# osd.net
KiCad netlist of a schematic drawn in Altium Designer
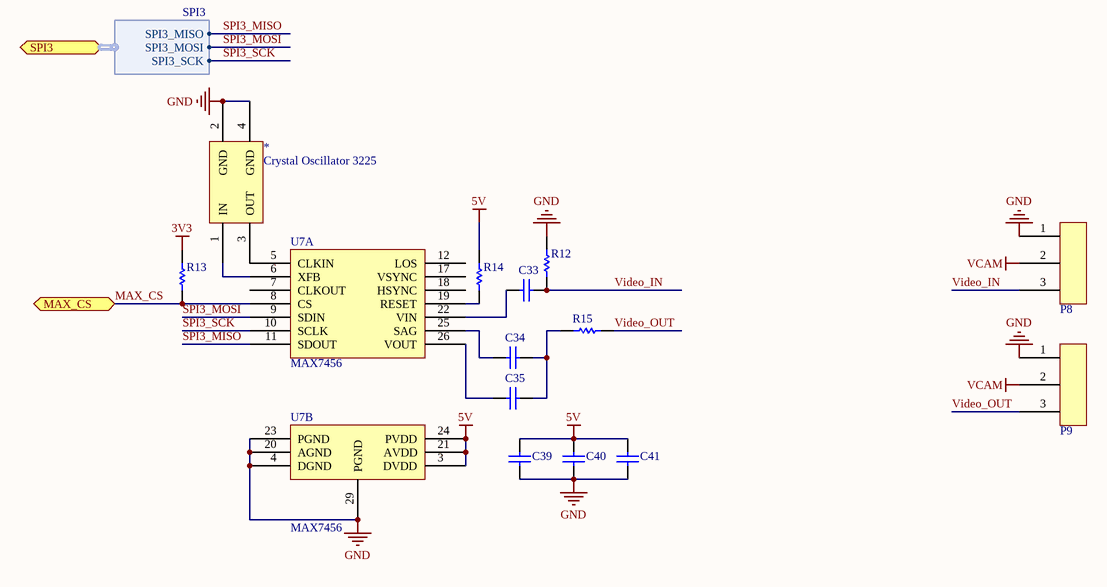
[diagram p0: osd.SchDoc]

(export (version "E")
  (design (tool "Eeschema 10.0.6"))
  (components
    (comp (ref "*")
      (value "Crystal Oscillator 3225")
      (footprint "TSX-3225")
      (description "TSX-3225")
      (libsource (lib "other") (part "TSX-3225"))
    )
    (comp (ref "C33")
      (value "CAP 100nF 25V 0603(1608)")
      (footprint "CAPC0603(1608)100_N")
      (description "CAP 100nF 25V ±20% 0603 (1608 Metric) Thickness 1mm SMD")
      (fields (field (name "TOLERANCE") "Â±20%"))
      (libsource (lib "Altium Content Vault") (part "CAP"))
    )
    (comp (ref "C34")
      (value "CAP 47uF 16V 1206(3216)")
      (footprint "CAPC1206(3216)190_M")
      (description "CAP 47uF 16V ±20% 1206 (3216 Metric) Thickness 1.9mm SMD")
      (fields (field (name "TOLERANCE") "Â±20%"))
      (libsource (lib "Altium Content Vault") (part "CAP"))
    )
    (comp (ref "C35")
      (value "CAP 47uF 16V 1206(3216)")
      (footprint "CAPC1206(3216)190_M")
      (description "CAP 47uF 16V ±20% 1206 (3216 Metric) Thickness 1.9mm SMD")
      (fields (field (name "TOLERANCE") "Â±20%"))
      (libsource (lib "Altium Content Vault") (part "CAP"))
    )
    (comp (ref "C39")
      (value "CAP 100nF 35V 0402(1005)")
      (footprint "CAPC0402(1005)60_N")
      (description "CAP 100nF 35V ±10% 0402 (1005 Metric) Thickness 0.6mm SMD")
      (fields (field (name "TOLERANCE") "Â±10%"))
      (libsource (lib "Altium Content Vault") (part "CAP"))
    )
    (comp (ref "C40")
      (value "CAP 100nF 35V 0402(1005)")
      (footprint "CAPC0402(1005)60_N")
      (description "CAP 100nF 35V ±10% 0402 (1005 Metric) Thickness 0.6mm SMD")
      (fields (field (name "TOLERANCE") "Â±10%"))
      (libsource (lib "Altium Content Vault") (part "CAP"))
    )
    (comp (ref "C41")
      (value "CAP 100nF 35V 0402(1005)")
      (footprint "CAPC0402(1005)60_N")
      (description "CAP 100nF 35V ±10% 0402 (1005 Metric) Thickness 0.6mm SMD")
      (fields (field (name "TOLERANCE") "Â±10%"))
      (libsource (lib "Altium Content Vault") (part "CAP"))
    )
    (comp (ref "P8") (value "3 Pads") (footprint "3Pads") (libsource (lib "MyLib") (part "3 Pads")))
    (comp (ref "P9") (value "3 Pads") (footprint "3Pads") (libsource (lib "MyLib") (part "3 Pads")))
    (comp (ref "R12")
      (value "75R 5% 0603(1608)")
      (footprint "RESC0603(1608)_N")
      (description "75R 0.1W 5% 0603 (1608 Metric)  SMD")
      (fields (field (name "TOLERANCE") "5 %") (field (name "POWER") "0.1 W"))
      (libsource (lib "Altium Content Vault") (part "RES"))
    )
    (comp (ref "R13")
      (value "10K 5% 0402(1005)")
      (footprint "RESC0402(1005)_N")
      (description "10K 0.063W 5% 0402 (1005 Metric)  SMD")
      (fields (field (name "TOLERANCE") "5 %") (field (name "POWER") "0.063 W"))
      (libsource (lib "Altium Content Vault") (part "RES"))
    )
    (comp (ref "R14")
      (value "10K 5% 0402(1005)")
      (footprint "RESC0402(1005)_L")
      (description "10K 0.063W 5% 0402 (1005 Metric)  SMD")
      (fields (field (name "TOLERANCE") "5 %") (field (name "POWER") "0.063 W"))
      (libsource (lib "Altium Content Vault") (part "CMP-1011-00098-1"))
    )
    (comp (ref "R15")
      (value "75R 5% 0402(1005)")
      (footprint "RESC0402(1005)_L")
      (description "75R 0.063W 5% 0402 (1005 Metric)  SMD")
      (fields (field (name "POWER") "0.063 W") (field (name "TOLERANCE") "5 %"))
      (libsource (lib "Altium Content Vault") (part "RES"))
    )
    (comp (ref "U7") (value "MAX7456") (footprint "SOP28") (libsource (lib "") (part "MAX7456_1")))
  )
  (nets
    (net (code "2") (name "/MAX_CS") (class "Default")
      (node (ref "R13") (pin "1") (pinfunction "1_1") (pintype "passive"))
      (node (ref "U7") (pin "8") (pinfunction "CS_8") (pintype "passive"))
    )
    (net (code "3") (name "/SPI3_MISO") (class "Default")
      (node (ref "U7") (pin "11") (pinfunction "SDOUT_11") (pintype "passive"))
    )
    (net (code "4") (name "/SPI3_MOSI") (class "Default")
      (node (ref "U7") (pin "9") (pinfunction "SDIN_9") (pintype "passive"))
    )
    (net (code "5") (name "/SPI3_SCK") (class "Default")
      (node (ref "U7") (pin "10") (pinfunction "SCLK_10") (pintype "passive"))
    )
    (net (code "6") (name "/Video_IN") (class "Default")
      (node (ref "C33") (pin "2") (pinfunction "2_2") (pintype "passive"))
      (node (ref "P8") (pin "3") (pinfunction "3_3") (pintype "passive"))
      (node (ref "R12") (pin "1") (pinfunction "1_1") (pintype "passive"))
    )
    (net (code "7") (name "/Video_OUT") (class "Default")
      (node (ref "P9") (pin "3") (pinfunction "3_3") (pintype "passive"))
      (node (ref "R15") (pin "2") (pinfunction "2_2") (pintype "passive"))
    )
    (net (code "9") (name "3V3") (class "Default")
      (node (ref "R13") (pin "2") (pinfunction "2_2") (pintype "passive"))
    )
    (net (code "10") (name "5V") (class "Default")
      (node (ref "C39") (pin "2") (pinfunction "2_2") (pintype "passive"))
      (node (ref "C40") (pin "2") (pinfunction "2_2") (pintype "passive"))
      (node (ref "C41") (pin "2") (pinfunction "2_2") (pintype "passive"))
      (node (ref "R14") (pin "2") (pinfunction "2_2") (pintype "passive"))
      (node (ref "U7") (pin "21") (pinfunction "AVDD_21") (pintype "passive"))
      (node (ref "U7") (pin "24") (pinfunction "PVDD_24") (pintype "passive"))
      (node (ref "U7") (pin "3") (pinfunction "DVDD_3") (pintype "passive"))
    )
    (net (code "11") (name "GND") (class "Default")
      (node (ref "*") (pin "2") (pinfunction "GND_2") (pintype "passive"))
      (node (ref "*") (pin "4") (pinfunction "GND_4") (pintype "passive"))
      (node (ref "C39") (pin "1") (pinfunction "1_1") (pintype "passive"))
      (node (ref "C40") (pin "1") (pinfunction "1_1") (pintype "passive"))
      (node (ref "C41") (pin "1") (pinfunction "1_1") (pintype "passive"))
      (node (ref "P8") (pin "1") (pinfunction "1_1") (pintype "passive"))
      (node (ref "P9") (pin "1") (pinfunction "1_1") (pintype "passive"))
      (node (ref "R12") (pin "2") (pinfunction "2_2") (pintype "passive"))
      (node (ref "U7") (pin "20") (pinfunction "AGND_20") (pintype "passive"))
      (node (ref "U7") (pin "23") (pinfunction "PGND_23") (pintype "passive"))
      (node (ref "U7") (pin "29") (pinfunction "PGND_29") (pintype "passive"))
      (node (ref "U7") (pin "4") (pinfunction "DGND_4") (pintype "passive"))
    )
    (net (code "12") (name "Net-(*-IN)") (class "Default")
      (node (ref "*") (pin "1") (pinfunction "IN_1") (pintype "passive"))
      (node (ref "U7") (pin "6") (pinfunction "XFB_6") (pintype "passive"))
    )
    (net (code "13") (name "Net-(*-OUT)") (class "Default")
      (node (ref "*") (pin "3") (pinfunction "OUT_3") (pintype "passive"))
      (node (ref "U7") (pin "5") (pinfunction "CLKIN_5") (pintype "passive"))
    )
    (net (code "14") (name "Net-(C34-Pad2)") (class "Default")
      (node (ref "C34") (pin "2") (pinfunction "2_2") (pintype "passive"))
      (node (ref "C35") (pin "2") (pinfunction "2_2") (pintype "passive"))
      (node (ref "R15") (pin "1") (pinfunction "1_1") (pintype "passive"))
    )
    (net (code "15") (name "Net-(U7A-RESET)") (class "Default")
      (node (ref "R14") (pin "1") (pinfunction "1_1") (pintype "passive"))
      (node (ref "U7") (pin "19") (pinfunction "RESET_19") (pintype "passive"))
    )
    (net (code "16") (name "Net-(U7A-SAG)") (class "Default")
      (node (ref "C34") (pin "1") (pinfunction "1_1") (pintype "passive"))
      (node (ref "U7") (pin "25") (pinfunction "SAG_25") (pintype "passive"))
    )
    (net (code "17") (name "Net-(U7A-VIN)") (class "Default")
      (node (ref "C33") (pin "1") (pinfunction "1_1") (pintype "passive"))
      (node (ref "U7") (pin "22") (pinfunction "VIN_22") (pintype "passive"))
    )
    (net (code "18") (name "Net-(U7A-VOUT)") (class "Default")
      (node (ref "C35") (pin "1") (pinfunction "1_1") (pintype "passive"))
      (node (ref "U7") (pin "26") (pinfunction "VOUT_26") (pintype "passive"))
    )
    (net (code "19") (name "VCAM") (class "Default")
      (node (ref "P8") (pin "2") (pinfunction "2_2") (pintype "passive"))
      (node (ref "P9") (pin "2") (pinfunction "2_2") (pintype "passive"))
    )
    (net (code "20") (name "unconnected-(U7A-CLKOUT-Pad7)") (class "Default")
      (node (ref "U7") (pin "7") (pinfunction "CLKOUT_7") (pintype "passive"))
    )
    (net (code "21") (name "unconnected-(U7A-HSYNC-Pad18)") (class "Default")
      (node (ref "U7") (pin "18") (pinfunction "HSYNC_18") (pintype "passive"))
    )
    (net (code "22") (name "unconnected-(U7A-LOS-Pad12)") (class "Default")
      (node (ref "U7") (pin "12") (pinfunction "LOS_12") (pintype "passive"))
    )
    (net (code "23") (name "unconnected-(U7A-VSYNC-Pad17)") (class "Default")
      (node (ref "U7") (pin "17") (pinfunction "VSYNC_17") (pintype "passive"))
    )
  )
)
